# H-Bridge-control_sense.net
KiCad netlist of a schematic drawn in Altium Designer
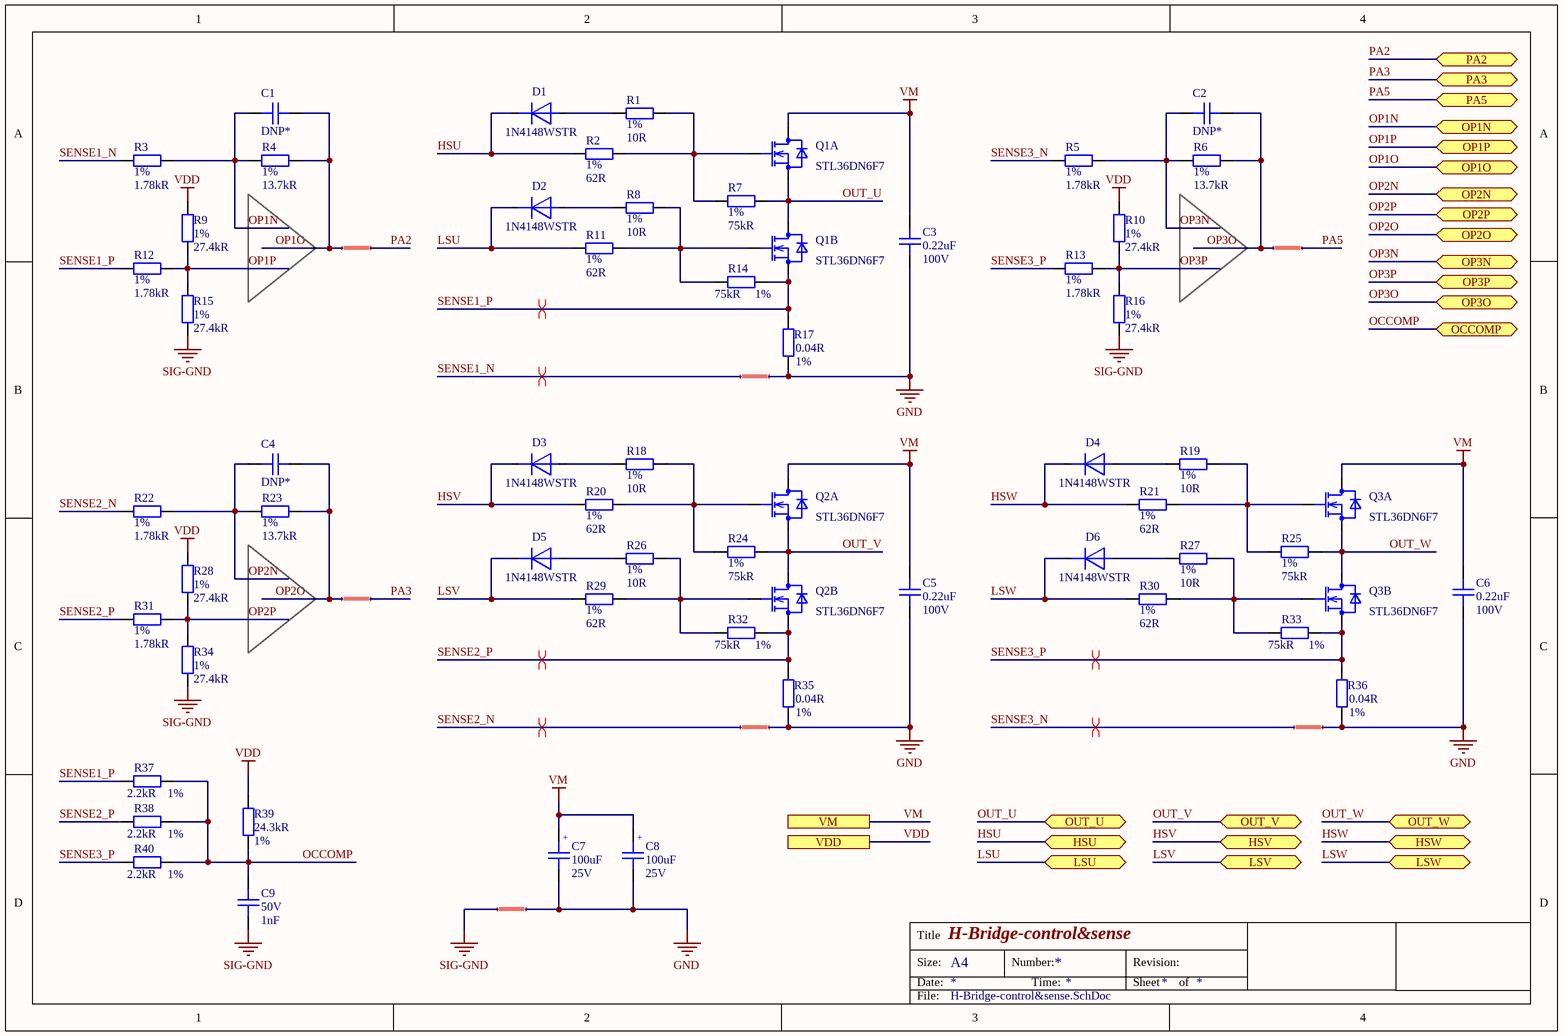
[diagram p0: H-Bridge-control&sense.SchDoc]

(export (version "E")
  (design (tool "Eeschema 10.0.6"))
  (components
    (comp (ref "C1")
      (value "DNP*")
      (footprint "C0402")
      (description "Placeholder for a 0402 capacitor")
      (libsource (lib "Control_Board_Model") (part "CAP CER NO_BOM 0402"))
    )
    (comp (ref "C2")
      (value "DNP*")
      (footprint "C0402")
      (description "Placeholder for a 0402 capacitor")
      (libsource (lib "Control_Board_Model") (part "CAP CER NO_BOM 0402"))
    )
    (comp (ref "C3")
      (value "CAP CER 220NF 100V X7R 0805")
      (footprint "C0805")
      (description "0.22 µF ±10% 100V Ceramic Capacitor X7R 0805 (2012 Metric)")
      (fields
        (field (name "MANUFACTURER") "KEMET")
        (field (name "MANUFACTURER PART NUMBER") "C0805C224K1RECAUTO")
        (field (name "CAPACITANCE") "0.22uF")
        (field (name "VOLTAGE RATING") "100V")
      )
      (libsource (lib "Control_Board_Model") (part "CAP CER 220NF 100V X7R 0805"))
    )
    (comp (ref "C4")
      (value "DNP*")
      (footprint "C0402")
      (description "Placeholder for a 0402 capacitor")
      (libsource (lib "Control_Board_Model") (part "CAP CER NO_BOM 0402"))
    )
    (comp (ref "C5")
      (value "CAP CER 220NF 100V X7R 0805")
      (footprint "C0805")
      (description "0.22 µF ±10% 100V Ceramic Capacitor X7R 0805 (2012 Metric)")
      (fields
        (field (name "MANUFACTURER") "KEMET")
        (field (name "MANUFACTURER PART NUMBER") "C0805C224K1RECAUTO")
        (field (name "CAPACITANCE") "0.22uF")
        (field (name "VOLTAGE RATING") "100V")
      )
      (libsource (lib "Control_Board_Model") (part "CAP CER 220NF 100V X7R 0805"))
    )
    (comp (ref "C6")
      (value "CAP CER 220NF 100V X7R 0805")
      (footprint "C0805")
      (description "0.22 µF ±10% 100V Ceramic Capacitor X7R 0805 (2012 Metric)")
      (fields
        (field (name "MANUFACTURER") "KEMET")
        (field (name "MANUFACTURER PART NUMBER") "C0805C224K1RECAUTO")
        (field (name "CAPACITANCE") "0.22uF")
        (field (name "VOLTAGE RATING") "100V")
      )
      (libsource (lib "Control_Board_Model") (part "CAP CER 220NF 100V X7R 0805"))
    )
    (comp (ref "C7")
      (value "CAP ALUM 100UF 20% 25V SMD")
      (footprint "WCAP-ASLI_8.3X6.5")
      (description "100 µF 25 V Aluminum Electrolytic Capacitors Radial, Can - SMD 260mOhm @ 100kHz 2000 Hrs @ 105°C")
      (fields
        (field (name "MANUFACTURER") "Panasonic Electronic Components")
        (field (name "MANUFACTURER PART NUMBER") "EEE-FK1E101V")
        (field (name "CAPACITANCE") "100uF")
        (field (name "RATED VOLTAGE") "25V")
      )
      (libsource (lib "Control_Board_Model") (part "CAP ALUM 220UF 20% 25V SMD"))
    )
    (comp (ref "C8")
      (value "CAP ALUM 100UF 20% 25V SMD")
      (footprint "WCAP-ASLI_8.3X6.5")
      (description "100 µF 25 V Aluminum Electrolytic Capacitors Radial, Can - SMD 260mOhm @ 100kHz 2000 Hrs @ 105°C")
      (fields
        (field (name "MANUFACTURER") "Panasonic Electronic Components")
        (field (name "MANUFACTURER PART NUMBER") "EEE-FK1E101V")
        (field (name "CAPACITANCE") "100uF")
        (field (name "RATED VOLTAGE") "25V")
      )
      (libsource (lib "Control_Board_Model") (part "CAP ALUM 220UF 20% 25V SMD"))
    )
    (comp (ref "C9")
      (value "CAP CER 1000PF 50V X7R 0402")
      (footprint "C0402")
      (description "1000pF ±10% 50V Ceramic Capacitor X7R 0402 (1005 Metric)")
      (fields
        (field (name "MANUFACTURER") "TDK-Lambda")
        (field (name "MANUFACTURER PART NUMBER") "C0402C102K5RACTU")
        (field (name "VOLTAGE RATING (DC)") "50V")
        (field (name "CAPACITANCE") "1nF")
      )
      (libsource (lib "Control_Board_Model") (part "CAP CER 1000PF 50V X7R 0402"))
    )
    (comp (ref "D1")
      (value "1N4148WSTR")
      (footprint "SOD-323F")
      (description "Diode Standard 75 V 300mA (DC) Surface Mount SOD-323")
      (fields (field (name "MANUFACTURER") "SMC Diode Solutions"))
      (libsource (lib "Control_Board_Model") (part "DIODE GEN PURP 75V 300MA SOD323"))
    )
    (comp (ref "D2")
      (value "1N4148WSTR")
      (footprint "SOD-323F")
      (description "Diode Standard 75 V 300mA (DC) Surface Mount SOD-323")
      (fields (field (name "MANUFACTURER") "SMC Diode Solutions"))
      (libsource (lib "Control_Board_Model") (part "DIODE GEN PURP 75V 300MA SOD323"))
    )
    (comp (ref "D3")
      (value "1N4148WSTR")
      (footprint "SOD-323F")
      (description "Diode Standard 75 V 300mA (DC) Surface Mount SOD-323")
      (fields (field (name "MANUFACTURER") "SMC Diode Solutions"))
      (libsource (lib "Control_Board_Model") (part "DIODE GEN PURP 75V 300MA SOD323"))
    )
    (comp (ref "D4")
      (value "1N4148WSTR")
      (footprint "SOD-323F")
      (description "Diode Standard 75 V 300mA (DC) Surface Mount SOD-323")
      (fields (field (name "MANUFACTURER") "SMC Diode Solutions"))
      (libsource (lib "Control_Board_Model") (part "DIODE GEN PURP 75V 300MA SOD323"))
    )
    (comp (ref "D5")
      (value "1N4148WSTR")
      (footprint "SOD-323F")
      (description "Diode Standard 75 V 300mA (DC) Surface Mount SOD-323")
      (fields (field (name "MANUFACTURER") "SMC Diode Solutions"))
      (libsource (lib "Control_Board_Model") (part "DIODE GEN PURP 75V 300MA SOD323"))
    )
    (comp (ref "D6")
      (value "1N4148WSTR")
      (footprint "SOD-323F")
      (description "Diode Standard 75 V 300mA (DC) Surface Mount SOD-323")
      (fields (field (name "MANUFACTURER") "SMC Diode Solutions"))
      (libsource (lib "Control_Board_Model") (part "DIODE GEN PURP 75V 300MA SOD323"))
    )
    (comp (ref "J1")
      (value "Net Tie")
      (footprint "Net Tie 6x30mil")
      (libsource (lib "BLDC_Motor_Driver") (part "Net Tie Line"))
    )
    (comp (ref "J2")
      (value "Net Tie")
      (footprint "Net Tie 6x30mil")
      (libsource (lib "BLDC_Motor_Driver") (part "Net Tie Line"))
    )
    (comp (ref "J3")
      (value "Net Tie")
      (footprint "Net Tie 6x30mil")
      (libsource (lib "BLDC_Motor_Driver") (part "Net Tie Line"))
    )
    (comp (ref "J4")
      (value "Net Tie")
      (footprint "Net Tie 6x30mil")
      (libsource (lib "BLDC_Motor_Driver") (part "Net Tie Line"))
    )
    (comp (ref "J5")
      (value "Net Tie")
      (footprint "Net Tie 6x30mil")
      (libsource (lib "BLDC_Motor_Driver") (part "Net Tie Line"))
    )
    (comp (ref "J6")
      (value "Net Tie")
      (footprint "Net Tie 6x30mil")
      (libsource (lib "BLDC_Motor_Driver") (part "Net Tie Line"))
    )
    (comp (ref "J7")
      (value "Net Tie")
      (footprint "Net Tie 6x30mil")
      (libsource (lib "BLDC_Motor_Driver") (part "Net Tie Line"))
    )
    (comp (ref "Q1")
      (value "STL36DN6F7")
      (footprint "PowerFlat™ (5x6)")
      (description "Mosfet Array 2 N-Channel (Dual) 60V 33A (Tc) 58W Surface Mount PowerFlat™ (5x6)")
      (fields (field (name "MANUFACTURER") "STMicroelectronics"))
      (libsource (lib "Control_Board_Model") (part "ARRAY MOSFET 2N-CH 60V 33A POWERFLAT"))
    )
    (comp (ref "Q2")
      (value "STL36DN6F7")
      (footprint "PowerFlat™ (5x6)")
      (description "Mosfet Array 2 N-Channel (Dual) 60V 33A (Tc) 58W Surface Mount PowerFlat™ (5x6)")
      (fields (field (name "MANUFACTURER") "STMicroelectronics"))
      (libsource (lib "Control_Board_Model") (part "ARRAY MOSFET 2N-CH 60V 33A POWERFLAT"))
    )
    (comp (ref "Q3")
      (value "STL36DN6F7")
      (footprint "PowerFlat™ (5x6)")
      (description "Mosfet Array 2 N-Channel (Dual) 60V 33A (Tc) 58W Surface Mount PowerFlat™ (5x6)")
      (fields (field (name "MANUFACTURER") "STMicroelectronics"))
      (libsource (lib "Control_Board_Model") (part "ARRAY MOSFET 2N-CH 60V 33A POWERFLAT"))
    )
    (comp (ref "R1")
      (value "RES SMD 10 OHM 1% 1/16W 0402")
      (footprint "R0402")
      (fields
        (field (name "MANUFACTURER") "Yageo")
        (field (name "MANUFACTURER PART NUMBER") "AC0402FR-0710RL")
        (field (name "TOLERANCE") "1%")
        (field (name "RESISTANCE") "10R")
      )
      (libsource (lib "Control_Board_Model") (part "RES SMD 10 OHM 1% 1/16W 0402"))
    )
    (comp (ref "R2")
      (value "RES SMD 62 OHM 1% 1/16W 0402")
      (footprint "R0402")
      (fields
        (field (name "MANUFACTURER") "Yageo")
        (field (name "MANUFACTURER PART NUMBER") "AC0402FR-0762RL")
        (field (name "TOLERANCE") "1%")
        (field (name "RESISTANCE") "62R")
      )
      (libsource (lib "Control_Board_Model") (part "RES SMD 62 OHM 1% 1/16W 0402"))
    )
    (comp (ref "R3")
      (value "RES SMD 1.78K OHM 1% 1/16W 0402")
      (footprint "R0402")
      (fields
        (field (name "MANUFACTURER") "Yageo")
        (field (name "MANUFACTURER PART NUMBER") "AC0402FR-071K78L")
        (field (name "TOLERANCE") "1%")
        (field (name "RESISTANCE") "1.78kR")
      )
      (libsource (lib "Control_Board_Model") (part "RES SMD 1.78K OHM 1% 1/16W 0402"))
    )
    (comp (ref "R4")
      (value "RES SMD 13.7K OHM 1% 1/16W 0402")
      (footprint "R0402")
      (fields
        (field (name "MANUFACTURER") "Yageo")
        (field (name "MANUFACTURER PART NUMBER") "AC0402FR-0713K7L")
        (field (name "TOLERANCE") "1%")
        (field (name "RESISTANCE") "13.7kR")
      )
      (libsource (lib "Control_Board_Model") (part "RES SMD 13.7K OHM 1% 1/16W 0402"))
    )
    (comp (ref "R5")
      (value "RES SMD 1.78K OHM 1% 1/16W 0402")
      (footprint "R0402")
      (fields
        (field (name "MANUFACTURER") "Yageo")
        (field (name "MANUFACTURER PART NUMBER") "AC0402FR-071K78L")
        (field (name "TOLERANCE") "1%")
        (field (name "RESISTANCE") "1.78kR")
      )
      (libsource (lib "Control_Board_Model") (part "RES SMD 1.78K OHM 1% 1/16W 0402"))
    )
    (comp (ref "R6")
      (value "RES SMD 13.7K OHM 1% 1/16W 0402")
      (footprint "R0402")
      (fields
        (field (name "MANUFACTURER") "Yageo")
        (field (name "MANUFACTURER PART NUMBER") "AC0402FR-0713K7L")
        (field (name "TOLERANCE") "1%")
        (field (name "RESISTANCE") "13.7kR")
      )
      (libsource (lib "Control_Board_Model") (part "RES SMD 13.7K OHM 1% 1/16W 0402"))
    )
    (comp (ref "R7")
      (value "RES SMD 75K OHM 1% 1/16W 0402")
      (footprint "R0402")
      (description "75 kOhms ±1% 0.063W, 1/16W Chip Resistor 0402 (1005 Metric) Automotive AEC-Q200 Thick Film")
      (fields
        (field (name "MANUFACTURER") "Stackpole Electronics")
        (field (name "MANUFACTURER PART NUMBER") "RMCF0402FT75K0")
        (field (name "TOLERANCE") "1%")
        (field (name "RESISTANCE") "75kR")
      )
      (libsource (lib "Control_Board_Model") (part "RES SMD 75K OHM 1% 1/16W 0402"))
    )
    (comp (ref "R8")
      (value "RES SMD 10 OHM 1% 1/16W 0402")
      (footprint "R0402")
      (fields
        (field (name "MANUFACTURER") "Yageo")
        (field (name "MANUFACTURER PART NUMBER") "AC0402FR-0710RL")
        (field (name "TOLERANCE") "1%")
        (field (name "RESISTANCE") "10R")
      )
      (libsource (lib "Control_Board_Model") (part "RES SMD 10 OHM 1% 1/16W 0402"))
    )
    (comp (ref "R9")
      (value "RES SMD 27.4K OHM 1% 1/16W 0402")
      (footprint "R0402")
      (fields
        (field (name "MANUFACTURER") "Yageo")
        (field (name "MANUFACTURER PART NUMBER") "AC0402FR-0727K4L")
        (field (name "TOLERANCE") "1%")
        (field (name "RESISTANCE") "27.4kR")
      )
      (libsource (lib "Control_Board_Model") (part "RES SMD 27.4K OHM 1% 1/16W 0402"))
    )
    (comp (ref "R10")
      (value "RES SMD 27.4K OHM 1% 1/16W 0402")
      (footprint "R0402")
      (fields
        (field (name "MANUFACTURER") "Yageo")
        (field (name "MANUFACTURER PART NUMBER") "AC0402FR-0727K4L")
        (field (name "TOLERANCE") "1%")
        (field (name "RESISTANCE") "27.4kR")
      )
      (libsource (lib "Control_Board_Model") (part "RES SMD 27.4K OHM 1% 1/16W 0402"))
    )
    (comp (ref "R11")
      (value "RES SMD 62 OHM 1% 1/16W 0402")
      (footprint "R0402")
      (fields
        (field (name "MANUFACTURER") "Yageo")
        (field (name "MANUFACTURER PART NUMBER") "AC0402FR-0762RL")
        (field (name "TOLERANCE") "1%")
        (field (name "RESISTANCE") "62R")
      )
      (libsource (lib "Control_Board_Model") (part "RES SMD 62 OHM 1% 1/16W 0402"))
    )
    (comp (ref "R12")
      (value "RES SMD 1.78K OHM 1% 1/16W 0402")
      (footprint "R0402")
      (fields
        (field (name "MANUFACTURER") "Yageo")
        (field (name "MANUFACTURER PART NUMBER") "AC0402FR-071K78L")
        (field (name "TOLERANCE") "1%")
        (field (name "RESISTANCE") "1.78kR")
      )
      (libsource (lib "Control_Board_Model") (part "RES SMD 1.78K OHM 1% 1/16W 0402"))
    )
    (comp (ref "R13")
      (value "RES SMD 1.78K OHM 1% 1/16W 0402")
      (footprint "R0402")
      (fields
        (field (name "MANUFACTURER") "Yageo")
        (field (name "MANUFACTURER PART NUMBER") "AC0402FR-071K78L")
        (field (name "TOLERANCE") "1%")
        (field (name "RESISTANCE") "1.78kR")
      )
      (libsource (lib "Control_Board_Model") (part "RES SMD 1.78K OHM 1% 1/16W 0402"))
    )
    (comp (ref "R14")
      (value "RES SMD 75K OHM 1% 1/16W 0402")
      (footprint "R0402")
      (description "75 kOhms ±1% 0.063W, 1/16W Chip Resistor 0402 (1005 Metric) Automotive AEC-Q200 Thick Film")
      (fields
        (field (name "MANUFACTURER") "Stackpole Electronics")
        (field (name "MANUFACTURER PART NUMBER") "RMCF0402FT75K0")
        (field (name "TOLERANCE") "1%")
        (field (name "RESISTANCE") "75kR")
      )
      (libsource (lib "Control_Board_Model") (part "RES SMD 75K OHM 1% 1/16W 0402"))
    )
    (comp (ref "R15")
      (value "RES SMD 27.4K OHM 1% 1/16W 0402")
      (footprint "R0402")
      (fields
        (field (name "MANUFACTURER") "Yageo")
        (field (name "MANUFACTURER PART NUMBER") "AC0402FR-0727K4L")
        (field (name "TOLERANCE") "1%")
        (field (name "RESISTANCE") "27.4kR")
      )
      (libsource (lib "Control_Board_Model") (part "RES SMD 27.4K OHM 1% 1/16W 0402"))
    )
    (comp (ref "R16")
      (value "RES SMD 27.4K OHM 1% 1/16W 0402")
      (footprint "R0402")
      (fields
        (field (name "MANUFACTURER") "Yageo")
        (field (name "MANUFACTURER PART NUMBER") "AC0402FR-0727K4L")
        (field (name "TOLERANCE") "1%")
        (field (name "RESISTANCE") "27.4kR")
      )
      (libsource (lib "Control_Board_Model") (part "RES SMD 27.4K OHM 1% 1/16W 0402"))
    )
    (comp (ref "R17")
      (value "RES 0.04 OHM 1% 2W  2512")
      (footprint "R2512")
      (description "40 mOhms ±1% 2W Chip Resistor 2512 (6432 Metric) Current Sense, Non-Inductive Metal Element")
      (fields
        (field (name "MANUFACTURER") "Stackpole Electronics Inc")
        (field (name "MANUFACTURER PART NUMBER") "CSR2512A0R04F")
        (field (name "TOLERANCE") "1%")
        (field (name "RESISTANCE") "0.04R")
      )
      (libsource (lib "Control_Board_Model") (part "RES 0.04 OHM 1% 2W  2512"))
    )
    (comp (ref "R18")
      (value "RES SMD 10 OHM 1% 1/16W 0402")
      (footprint "R0402")
      (fields
        (field (name "MANUFACTURER") "Yageo")
        (field (name "MANUFACTURER PART NUMBER") "AC0402FR-0710RL")
        (field (name "TOLERANCE") "1%")
        (field (name "RESISTANCE") "10R")
      )
      (libsource (lib "Control_Board_Model") (part "RES SMD 10 OHM 1% 1/16W 0402"))
    )
    (comp (ref "R19")
      (value "RES SMD 10 OHM 1% 1/16W 0402")
      (footprint "R0402")
      (fields
        (field (name "MANUFACTURER") "Yageo")
        (field (name "MANUFACTURER PART NUMBER") "AC0402FR-0710RL")
        (field (name "TOLERANCE") "1%")
        (field (name "RESISTANCE") "10R")
      )
      (libsource (lib "Control_Board_Model") (part "RES SMD 10 OHM 1% 1/16W 0402"))
    )
    (comp (ref "R20")
      (value "RES SMD 62 OHM 1% 1/16W 0402")
      (footprint "R0402")
      (fields
        (field (name "MANUFACTURER") "Yageo")
        (field (name "MANUFACTURER PART NUMBER") "AC0402FR-0762RL")
        (field (name "TOLERANCE") "1%")
        (field (name "RESISTANCE") "62R")
      )
      (libsource (lib "Control_Board_Model") (part "RES SMD 62 OHM 1% 1/16W 0402"))
    )
    (comp (ref "R21")
      (value "RES SMD 62 OHM 1% 1/16W 0402")
      (footprint "R0402")
      (fields
        (field (name "MANUFACTURER") "Yageo")
        (field (name "MANUFACTURER PART NUMBER") "AC0402FR-0762RL")
        (field (name "TOLERANCE") "1%")
        (field (name "RESISTANCE") "62R")
      )
      (libsource (lib "Control_Board_Model") (part "RES SMD 62 OHM 1% 1/16W 0402"))
    )
    (comp (ref "R22")
      (value "RES SMD 1.78K OHM 1% 1/16W 0402")
      (footprint "R0402")
      (fields
        (field (name "MANUFACTURER") "Yageo")
        (field (name "MANUFACTURER PART NUMBER") "AC0402FR-071K78L")
        (field (name "TOLERANCE") "1%")
        (field (name "RESISTANCE") "1.78kR")
      )
      (libsource (lib "Control_Board_Model") (part "RES SMD 1.78K OHM 1% 1/16W 0402"))
    )
    (comp (ref "R23")
      (value "RES SMD 13.7K OHM 1% 1/16W 0402")
      (footprint "R0402")
      (fields
        (field (name "MANUFACTURER") "Yageo")
        (field (name "MANUFACTURER PART NUMBER") "AC0402FR-0713K7L")
        (field (name "TOLERANCE") "1%")
        (field (name "RESISTANCE") "13.7kR")
      )
      (libsource (lib "Control_Board_Model") (part "RES SMD 13.7K OHM 1% 1/16W 0402"))
    )
    (comp (ref "R24")
      (value "RES SMD 75K OHM 1% 1/16W 0402")
      (footprint "R0402")
      (description "75 kOhms ±1% 0.063W, 1/16W Chip Resistor 0402 (1005 Metric) Automotive AEC-Q200 Thick Film")
      (fields
        (field (name "MANUFACTURER") "Stackpole Electronics")
        (field (name "MANUFACTURER PART NUMBER") "RMCF0402FT75K0")
        (field (name "TOLERANCE") "1%")
        (field (name "RESISTANCE") "75kR")
      )
      (libsource (lib "Control_Board_Model") (part "RES SMD 75K OHM 1% 1/16W 0402"))
    )
    (comp (ref "R25")
      (value "RES SMD 75K OHM 1% 1/16W 0402")
      (footprint "R0402")
      (description "75 kOhms ±1% 0.063W, 1/16W Chip Resistor 0402 (1005 Metric) Automotive AEC-Q200 Thick Film")
      (fields
        (field (name "MANUFACTURER") "Stackpole Electronics")
        (field (name "MANUFACTURER PART NUMBER") "RMCF0402FT75K0")
        (field (name "TOLERANCE") "1%")
        (field (name "RESISTANCE") "75kR")
      )
      (libsource (lib "Control_Board_Model") (part "RES SMD 75K OHM 1% 1/16W 0402"))
    )
    (comp (ref "R26")
      (value "RES SMD 10 OHM 1% 1/16W 0402")
      (footprint "R0402")
      (fields
        (field (name "MANUFACTURER") "Yageo")
        (field (name "MANUFACTURER PART NUMBER") "AC0402FR-0710RL")
        (field (name "TOLERANCE") "1%")
        (field (name "RESISTANCE") "10R")
      )
      (libsource (lib "Control_Board_Model") (part "RES SMD 10 OHM 1% 1/16W 0402"))
    )
    (comp (ref "R27")
      (value "RES SMD 10 OHM 1% 1/16W 0402")
      (footprint "R0402")
      (fields
        (field (name "MANUFACTURER") "Yageo")
        (field (name "MANUFACTURER PART NUMBER") "AC0402FR-0710RL")
        (field (name "TOLERANCE") "1%")
        (field (name "RESISTANCE") "10R")
      )
      (libsource (lib "Control_Board_Model") (part "RES SMD 10 OHM 1% 1/16W 0402"))
    )
    (comp (ref "R28")
      (value "RES SMD 27.4K OHM 1% 1/16W 0402")
      (footprint "R0402")
      (fields
        (field (name "MANUFACTURER") "Yageo")
        (field (name "MANUFACTURER PART NUMBER") "AC0402FR-0727K4L")
        (field (name "TOLERANCE") "1%")
        (field (name "RESISTANCE") "27.4kR")
      )
      (libsource (lib "Control_Board_Model") (part "RES SMD 27.4K OHM 1% 1/16W 0402"))
    )
    (comp (ref "R29")
      (value "RES SMD 62 OHM 1% 1/16W 0402")
      (footprint "R0402")
      (fields
        (field (name "MANUFACTURER") "Yageo")
        (field (name "MANUFACTURER PART NUMBER") "AC0402FR-0762RL")
        (field (name "TOLERANCE") "1%")
        (field (name "RESISTANCE") "62R")
      )
      (libsource (lib "Control_Board_Model") (part "RES SMD 62 OHM 1% 1/16W 0402"))
    )
    (comp (ref "R30")
      (value "RES SMD 62 OHM 1% 1/16W 0402")
      (footprint "R0402")
      (fields
        (field (name "MANUFACTURER") "Yageo")
        (field (name "MANUFACTURER PART NUMBER") "AC0402FR-0762RL")
        (field (name "TOLERANCE") "1%")
        (field (name "RESISTANCE") "62R")
      )
      (libsource (lib "Control_Board_Model") (part "RES SMD 62 OHM 1% 1/16W 0402"))
    )
    (comp (ref "R31")
      (value "RES SMD 1.78K OHM 1% 1/16W 0402")
      (footprint "R0402")
      (fields
        (field (name "MANUFACTURER") "Yageo")
        (field (name "MANUFACTURER PART NUMBER") "AC0402FR-071K78L")
        (field (name "TOLERANCE") "1%")
        (field (name "RESISTANCE") "1.78kR")
      )
      (libsource (lib "Control_Board_Model") (part "RES SMD 1.78K OHM 1% 1/16W 0402"))
    )
    (comp (ref "R32")
      (value "RES SMD 75K OHM 1% 1/16W 0402")
      (footprint "R0402")
      (description "75 kOhms ±1% 0.063W, 1/16W Chip Resistor 0402 (1005 Metric) Automotive AEC-Q200 Thick Film")
      (fields
        (field (name "MANUFACTURER") "Stackpole Electronics")
        (field (name "MANUFACTURER PART NUMBER") "RMCF0402FT75K0")
        (field (name "TOLERANCE") "1%")
        (field (name "RESISTANCE") "75kR")
      )
      (libsource (lib "Control_Board_Model") (part "RES SMD 75K OHM 1% 1/16W 0402"))
    )
    (comp (ref "R33")
      (value "RES SMD 75K OHM 1% 1/16W 0402")
      (footprint "R0402")
      (description "75 kOhms ±1% 0.063W, 1/16W Chip Resistor 0402 (1005 Metric) Automotive AEC-Q200 Thick Film")
      (fields
        (field (name "MANUFACTURER") "Stackpole Electronics")
        (field (name "MANUFACTURER PART NUMBER") "RMCF0402FT75K0")
        (field (name "TOLERANCE") "1%")
        (field (name "RESISTANCE") "75kR")
      )
      (libsource (lib "Control_Board_Model") (part "RES SMD 75K OHM 1% 1/16W 0402"))
    )
    (comp (ref "R34")
      (value "RES SMD 27.4K OHM 1% 1/16W 0402")
      (footprint "R0402")
      (fields
        (field (name "MANUFACTURER") "Yageo")
        (field (name "MANUFACTURER PART NUMBER") "AC0402FR-0727K4L")
        (field (name "TOLERANCE") "1%")
        (field (name "RESISTANCE") "27.4kR")
      )
      (libsource (lib "Control_Board_Model") (part "RES SMD 27.4K OHM 1% 1/16W 0402"))
    )
    (comp (ref "R35")
      (value "RES 0.04 OHM 1% 2W  2512")
      (footprint "R2512")
      (description "40 mOhms ±1% 2W Chip Resistor 2512 (6432 Metric) Current Sense, Non-Inductive Metal Element")
      (fields
        (field (name "MANUFACTURER") "Stackpole Electronics Inc")
        (field (name "MANUFACTURER PART NUMBER") "CSR2512A0R04F")
        (field (name "TOLERANCE") "1%")
        (field (name "RESISTANCE") "0.04R")
      )
      (libsource (lib "Control_Board_Model") (part "RES 0.04 OHM 1% 2W  2512"))
    )
    (comp (ref "R36")
      (value "RES 0.04 OHM 1% 2W  2512")
      (footprint "R2512")
      (description "40 mOhms ±1% 2W Chip Resistor 2512 (6432 Metric) Current Sense, Non-Inductive Metal Element")
      (fields
        (field (name "MANUFACTURER") "Stackpole Electronics Inc")
        (field (name "MANUFACTURER PART NUMBER") "CSR2512A0R04F")
        (field (name "TOLERANCE") "1%")
        (field (name "RESISTANCE") "0.04R")
      )
      (libsource (lib "Control_Board_Model") (part "RES 0.04 OHM 1% 2W  2512"))
    )
    (comp (ref "R37")
      (value "RES SMD 2.2K OHM 1% 1/16W 0402")
      (footprint "R0402")
      (fields
        (field (name "MANUFACTURER") "Yageo")
        (field (name "MANUFACTURER PART NUMBER") "AC0402FR-072K2L")
        (field (name "TOLERANCE") "1%")
        (field (name "RESISTANCE") "2.2kR")
      )
      (libsource (lib "Control_Board_Model") (part "RES SMD 2.2K OHM 1% 1/16W 0402"))
    )
    (comp (ref "R38")
      (value "RES SMD 2.2K OHM 1% 1/16W 0402")
      (footprint "R0402")
      (fields
        (field (name "MANUFACTURER") "Yageo")
        (field (name "MANUFACTURER PART NUMBER") "AC0402FR-072K2L")
        (field (name "TOLERANCE") "1%")
        (field (name "RESISTANCE") "2.2kR")
      )
      (libsource (lib "Control_Board_Model") (part "RES SMD 2.2K OHM 1% 1/16W 0402"))
    )
    (comp (ref "R39")
      (value "RES SMD 24.3K OHM 1% 1/16W 0402")
      (footprint "R0402")
      (description "24.3 ±1% 0.063W, 1/16W Chip Resistor 0402 (1005 Metric) Moisture Resistant Thick Film")
      (fields
        (field (name "MANUFACTURER") "Yageo")
        (field (name "MANUFACTURER PART NUMBER") "RC0402FR-0724K3L")
        (field (name "RESISTANCE") "24.3kR")
        (field (name "TOLERANCE") "1%")
      )
      (libsource (lib "Control_Board_Model") (part "RES SMD 24.3K OHM 1% 1/16W 0402"))
    )
    (comp (ref "R40")
      (value "RES SMD 2.2K OHM 1% 1/16W 0402")
      (footprint "R0402")
      (fields
        (field (name "MANUFACTURER") "Yageo")
        (field (name "MANUFACTURER PART NUMBER") "AC0402FR-072K2L")
        (field (name "TOLERANCE") "1%")
        (field (name "RESISTANCE") "2.2kR")
      )
      (libsource (lib "Control_Board_Model") (part "RES SMD 2.2K OHM 1% 1/16W 0402"))
    )
  )
  (nets
    (net (code "1") (name "/HSU") (class "Default")
      (node (ref "D1") (pin "1") (pinfunction "K_1") (pintype "passive"))
      (node (ref "R2") (pin "1") (pinfunction "1_1") (pintype "passive"))
    )
    (net (code "2") (name "/HSV") (class "Default")
      (node (ref "D3") (pin "1") (pinfunction "K_1") (pintype "passive"))
      (node (ref "R20") (pin "1") (pinfunction "1_1") (pintype "passive"))
    )
    (net (code "3") (name "/HSW") (class "Default")
      (node (ref "D4") (pin "1") (pinfunction "K_1") (pintype "passive"))
      (node (ref "R21") (pin "1") (pinfunction "1_1") (pintype "passive"))
    )
    (net (code "4") (name "/LSU") (class "Default")
      (node (ref "D2") (pin "1") (pinfunction "K_1") (pintype "passive"))
      (node (ref "R11") (pin "1") (pinfunction "1_1") (pintype "passive"))
    )
    (net (code "5") (name "/LSV") (class "Default")
      (node (ref "D5") (pin "1") (pinfunction "K_1") (pintype "passive"))
      (node (ref "R29") (pin "1") (pinfunction "1_1") (pintype "passive"))
    )
    (net (code "6") (name "/LSW") (class "Default")
      (node (ref "D6") (pin "1") (pinfunction "K_1") (pintype "passive"))
      (node (ref "R30") (pin "1") (pinfunction "1_1") (pintype "passive"))
    )
    (net (code "7") (name "/OCCOMP") (class "Default")
      (node (ref "C9") (pin "2") (pinfunction "2_2") (pintype "passive"))
      (node (ref "R37") (pin "2") (pinfunction "2_2") (pintype "passive"))
      (node (ref "R38") (pin "2") (pinfunction "2_2") (pintype "passive"))
      (node (ref "R39") (pin "2") (pinfunction "2_2") (pintype "passive"))
      (node (ref "R40") (pin "2") (pinfunction "2_2") (pintype "passive"))
    )
    (net (code "8") (name "/OP1N") (class "Default")
      (node (ref "C1") (pin "1") (pinfunction "1_1") (pintype "passive"))
      (node (ref "R3") (pin "2") (pinfunction "2_2") (pintype "passive"))
      (node (ref "R4") (pin "1") (pinfunction "1_1") (pintype "passive"))
    )
    (net (code "9") (name "/OP1O") (class "Default")
      (node (ref "C1") (pin "2") (pinfunction "2_2") (pintype "passive"))
      (node (ref "J1") (pin "2") (pintype "passive"))
      (node (ref "R4") (pin "2") (pinfunction "2_2") (pintype "passive"))
    )
    (net (code "10") (name "/OP1P") (class "Default")
      (node (ref "R12") (pin "2") (pinfunction "2_2") (pintype "passive"))
      (node (ref "R15") (pin "2") (pinfunction "2_2") (pintype "passive"))
      (node (ref "R9") (pin "1") (pinfunction "1_1") (pintype "passive"))
    )
    (net (code "11") (name "/OP2N") (class "Default")
      (node (ref "C4") (pin "1") (pinfunction "1_1") (pintype "passive"))
      (node (ref "R22") (pin "2") (pinfunction "2_2") (pintype "passive"))
      (node (ref "R23") (pin "1") (pinfunction "1_1") (pintype "passive"))
    )
    (net (code "12") (name "/OP2O") (class "Default")
      (node (ref "C4") (pin "2") (pinfunction "2_2") (pintype "passive"))
      (node (ref "J4") (pin "2") (pintype "passive"))
      (node (ref "R23") (pin "2") (pinfunction "2_2") (pintype "passive"))
    )
    (net (code "13") (name "/OP2P") (class "Default")
      (node (ref "R28") (pin "1") (pinfunction "1_1") (pintype "passive"))
      (node (ref "R31") (pin "2") (pinfunction "2_2") (pintype "passive"))
      (node (ref "R34") (pin "2") (pinfunction "2_2") (pintype "passive"))
    )
    (net (code "14") (name "/OP3N") (class "Default")
      (node (ref "C2") (pin "1") (pinfunction "1_1") (pintype "passive"))
      (node (ref "R5") (pin "2") (pinfunction "2_2") (pintype "passive"))
      (node (ref "R6") (pin "1") (pinfunction "1_1") (pintype "passive"))
    )
    (net (code "15") (name "/OP3O") (class "Default")
      (node (ref "C2") (pin "2") (pinfunction "2_2") (pintype "passive"))
      (node (ref "J2") (pin "2") (pintype "passive"))
      (node (ref "R6") (pin "2") (pinfunction "2_2") (pintype "passive"))
    )
    (net (code "16") (name "/OP3P") (class "Default")
      (node (ref "R10") (pin "1") (pinfunction "1_1") (pintype "passive"))
      (node (ref "R13") (pin "2") (pinfunction "2_2") (pintype "passive"))
      (node (ref "R16") (pin "2") (pinfunction "2_2") (pintype "passive"))
    )
    (net (code "17") (name "/OUT_U") (class "Default")
      (node (ref "Q1") (pin "3") (pinfunction "S1_3") (pintype "passive"))
      (node (ref "Q1") (pin "7") (pinfunction "D1_7") (pintype "passive"))
      (node (ref "R7") (pin "2") (pinfunction "2_2") (pintype "passive"))
    )
    (net (code "18") (name "/OUT_V") (class "Default")
      (node (ref "Q2") (pin "3") (pinfunction "S1_3") (pintype "passive"))
      (node (ref "Q2") (pin "7") (pinfunction "D1_7") (pintype "passive"))
      (node (ref "R24") (pin "2") (pinfunction "2_2") (pintype "passive"))
    )
    (net (code "19") (name "/OUT_W") (class "Default")
      (node (ref "Q3") (pin "3") (pinfunction "S1_3") (pintype "passive"))
      (node (ref "Q3") (pin "7") (pinfunction "D1_7") (pintype "passive"))
      (node (ref "R25") (pin "2") (pinfunction "2_2") (pintype "passive"))
    )
    (net (code "20") (name "/PA2") (class "Default") (node (ref "J1") (pin "1") (pintype "passive")))
    (net (code "21") (name "/PA3") (class "Default") (node (ref "J4") (pin "1") (pintype "passive")))
    (net (code "22") (name "/PA5") (class "Default") (node (ref "J2") (pin "1") (pintype "passive")))
    (net (code "23") (name "/SENSE1_N") (class "Default")
      (node (ref "J3") (pin "2") (pintype "passive"))
      (node (ref "R3") (pin "1") (pinfunction "1_1") (pintype "passive"))
    )
    (net (code "24") (name "/SENSE1_P") (class "Default")
      (node (ref "Q1") (pin "1") (pinfunction "S2_1") (pintype "passive"))
      (node (ref "R12") (pin "1") (pinfunction "1_1") (pintype "passive"))
      (node (ref "R14") (pin "2") (pinfunction "2_2") (pintype "passive"))
      (node (ref "R17") (pin "2") (pinfunction "2_2") (pintype "passive"))
      (node (ref "R37") (pin "1") (pinfunction "1_1") (pintype "passive"))
    )
    (net (code "25") (name "/SENSE2_N") (class "Default")
      (node (ref "J5") (pin "2") (pintype "passive"))
      (node (ref "R22") (pin "1") (pinfunction "1_1") (pintype "passive"))
    )
    (net (code "26") (name "/SENSE2_P") (class "Default")
      (node (ref "Q2") (pin "1") (pinfunction "S2_1") (pintype "passive"))
      (node (ref "R31") (pin "1") (pinfunction "1_1") (pintype "passive"))
      (node (ref "R32") (pin "2") (pinfunction "2_2") (pintype "passive"))
      (node (ref "R35") (pin "2") (pinfunction "2_2") (pintype "passive"))
      (node (ref "R38") (pin "1") (pinfunction "1_1") (pintype "passive"))
    )
    (net (code "27") (name "/SENSE3_N") (class "Default")
      (node (ref "J6") (pin "2") (pintype "passive"))
      (node (ref "R5") (pin "1") (pinfunction "1_1") (pintype "passive"))
    )
    (net (code "28") (name "/SENSE3_P") (class "Default")
      (node (ref "Q3") (pin "1") (pinfunction "S2_1") (pintype "passive"))
      (node (ref "R13") (pin "1") (pinfunction "1_1") (pintype "passive"))
      (node (ref "R33") (pin "2") (pinfunction "2_2") (pintype "passive"))
      (node (ref "R36") (pin "2") (pinfunction "2_2") (pintype "passive"))
      (node (ref "R40") (pin "1") (pinfunction "1_1") (pintype "passive"))
    )
    (net (code "29") (name "GND") (class "Default")
      (node (ref "C3") (pin "1") (pinfunction "1_1") (pintype "passive"))
      (node (ref "C5") (pin "1") (pinfunction "1_1") (pintype "passive"))
      (node (ref "C6") (pin "1") (pinfunction "1_1") (pintype "passive"))
      (node (ref "C7") (pin "2") (pinfunction "2_2") (pintype "passive"))
      (node (ref "C8") (pin "2") (pinfunction "2_2") (pintype "passive"))
      (node (ref "J3") (pin "1") (pintype "passive"))
      (node (ref "J5") (pin "1") (pintype "passive"))
      (node (ref "J6") (pin "1") (pintype "passive"))
      (node (ref "J7") (pin "1") (pintype "passive"))
      (node (ref "R17") (pin "1") (pinfunction "1_1") (pintype "passive"))
      (node (ref "R35") (pin "1") (pinfunction "1_1") (pintype "passive"))
      (node (ref "R36") (pin "1") (pinfunction "1_1") (pintype "passive"))
    )
    (net (code "30") (name "Net-(D1-A)") (class "Default")
      (node (ref "D1") (pin "2") (pinfunction "A_2") (pintype "passive"))
      (node (ref "R1") (pin "1") (pinfunction "1_1") (pintype "passive"))
    )
    (net (code "31") (name "Net-(D2-A)") (class "Default")
      (node (ref "D2") (pin "2") (pinfunction "A_2") (pintype "passive"))
      (node (ref "R8") (pin "1") (pinfunction "1_1") (pintype "passive"))
    )
    (net (code "32") (name "Net-(D3-A)") (class "Default")
      (node (ref "D3") (pin "2") (pinfunction "A_2") (pintype "passive"))
      (node (ref "R18") (pin "1") (pinfunction "1_1") (pintype "passive"))
    )
    (net (code "33") (name "Net-(D4-A)") (class "Default")
      (node (ref "D4") (pin "2") (pinfunction "A_2") (pintype "passive"))
      (node (ref "R19") (pin "1") (pinfunction "1_1") (pintype "passive"))
    )
    (net (code "34") (name "Net-(D5-A)") (class "Default")
      (node (ref "D5") (pin "2") (pinfunction "A_2") (pintype "passive"))
      (node (ref "R26") (pin "1") (pinfunction "1_1") (pintype "passive"))
    )
    (net (code "35") (name "Net-(D6-A)") (class "Default")
      (node (ref "D6") (pin "2") (pinfunction "A_2") (pintype "passive"))
      (node (ref "R27") (pin "1") (pinfunction "1_1") (pintype "passive"))
    )
    (net (code "36") (name "Net-(Q1A-G1)") (class "Default")
      (node (ref "Q1") (pin "4") (pinfunction "G1_4") (pintype "passive"))
      (node (ref "R1") (pin "2") (pinfunction "2_2") (pintype "passive"))
      (node (ref "R2") (pin "2") (pinfunction "2_2") (pintype "passive"))
      (node (ref "R7") (pin "1") (pinfunction "1_1") (pintype "passive"))
    )
    (net (code "37") (name "Net-(Q1B-G2)") (class "Default")
      (node (ref "Q1") (pin "2") (pinfunction "G2_2") (pintype "passive"))
      (node (ref "R11") (pin "2") (pinfunction "2_2") (pintype "passive"))
      (node (ref "R14") (pin "1") (pinfunction "1_1") (pintype "passive"))
      (node (ref "R8") (pin "2") (pinfunction "2_2") (pintype "passive"))
    )
    (net (code "38") (name "Net-(Q2A-G1)") (class "Default")
      (node (ref "Q2") (pin "4") (pinfunction "G1_4") (pintype "passive"))
      (node (ref "R18") (pin "2") (pinfunction "2_2") (pintype "passive"))
      (node (ref "R20") (pin "2") (pinfunction "2_2") (pintype "passive"))
      (node (ref "R24") (pin "1") (pinfunction "1_1") (pintype "passive"))
    )
    (net (code "39") (name "Net-(Q2B-G2)") (class "Default")
      (node (ref "Q2") (pin "2") (pinfunction "G2_2") (pintype "passive"))
      (node (ref "R26") (pin "2") (pinfunction "2_2") (pintype "passive"))
      (node (ref "R29") (pin "2") (pinfunction "2_2") (pintype "passive"))
      (node (ref "R32") (pin "1") (pinfunction "1_1") (pintype "passive"))
    )
    (net (code "40") (name "Net-(Q3A-G1)") (class "Default")
      (node (ref "Q3") (pin "4") (pinfunction "G1_4") (pintype "passive"))
      (node (ref "R19") (pin "2") (pinfunction "2_2") (pintype "passive"))
      (node (ref "R21") (pin "2") (pinfunction "2_2") (pintype "passive"))
      (node (ref "R25") (pin "1") (pinfunction "1_1") (pintype "passive"))
    )
    (net (code "41") (name "Net-(Q3B-G2)") (class "Default")
      (node (ref "Q3") (pin "2") (pinfunction "G2_2") (pintype "passive"))
      (node (ref "R27") (pin "2") (pinfunction "2_2") (pintype "passive"))
      (node (ref "R30") (pin "2") (pinfunction "2_2") (pintype "passive"))
      (node (ref "R33") (pin "1") (pinfunction "1_1") (pintype "passive"))
    )
    (net (code "42") (name "SIG-GND") (class "Default")
      (node (ref "C9") (pin "1") (pinfunction "1_1") (pintype "passive"))
      (node (ref "J7") (pin "2") (pintype "passive"))
      (node (ref "R15") (pin "1") (pinfunction "1_1") (pintype "passive"))
      (node (ref "R16") (pin "1") (pinfunction "1_1") (pintype "passive"))
      (node (ref "R34") (pin "1") (pinfunction "1_1") (pintype "passive"))
    )
    (net (code "43") (name "VDD") (class "Default")
      (node (ref "R10") (pin "2") (pinfunction "2_2") (pintype "passive"))
      (node (ref "R28") (pin "2") (pinfunction "2_2") (pintype "passive"))
      (node (ref "R39") (pin "1") (pinfunction "1_1") (pintype "passive"))
      (node (ref "R9") (pin "2") (pinfunction "2_2") (pintype "passive"))
    )
    (net (code "44") (name "VM") (class "Default")
      (node (ref "C3") (pin "2") (pinfunction "2_2") (pintype "passive"))
      (node (ref "C5") (pin "2") (pinfunction "2_2") (pintype "passive"))
      (node (ref "C6") (pin "2") (pinfunction "2_2") (pintype "passive"))
      (node (ref "C7") (pin "1") (pinfunction "1_1") (pintype "passive"))
      (node (ref "C8") (pin "1") (pinfunction "1_1") (pintype "passive"))
      (node (ref "Q1") (pin "5") (pinfunction "D1_5") (pintype "passive"))
      (node (ref "Q2") (pin "5") (pinfunction "D1_5") (pintype "passive"))
      (node (ref "Q3") (pin "5") (pinfunction "D1_5") (pintype "passive"))
    )
  )
)
